# Qwiic_OLED_Breakout.net
KiCad netlist of a schematic drawn in EAGLE
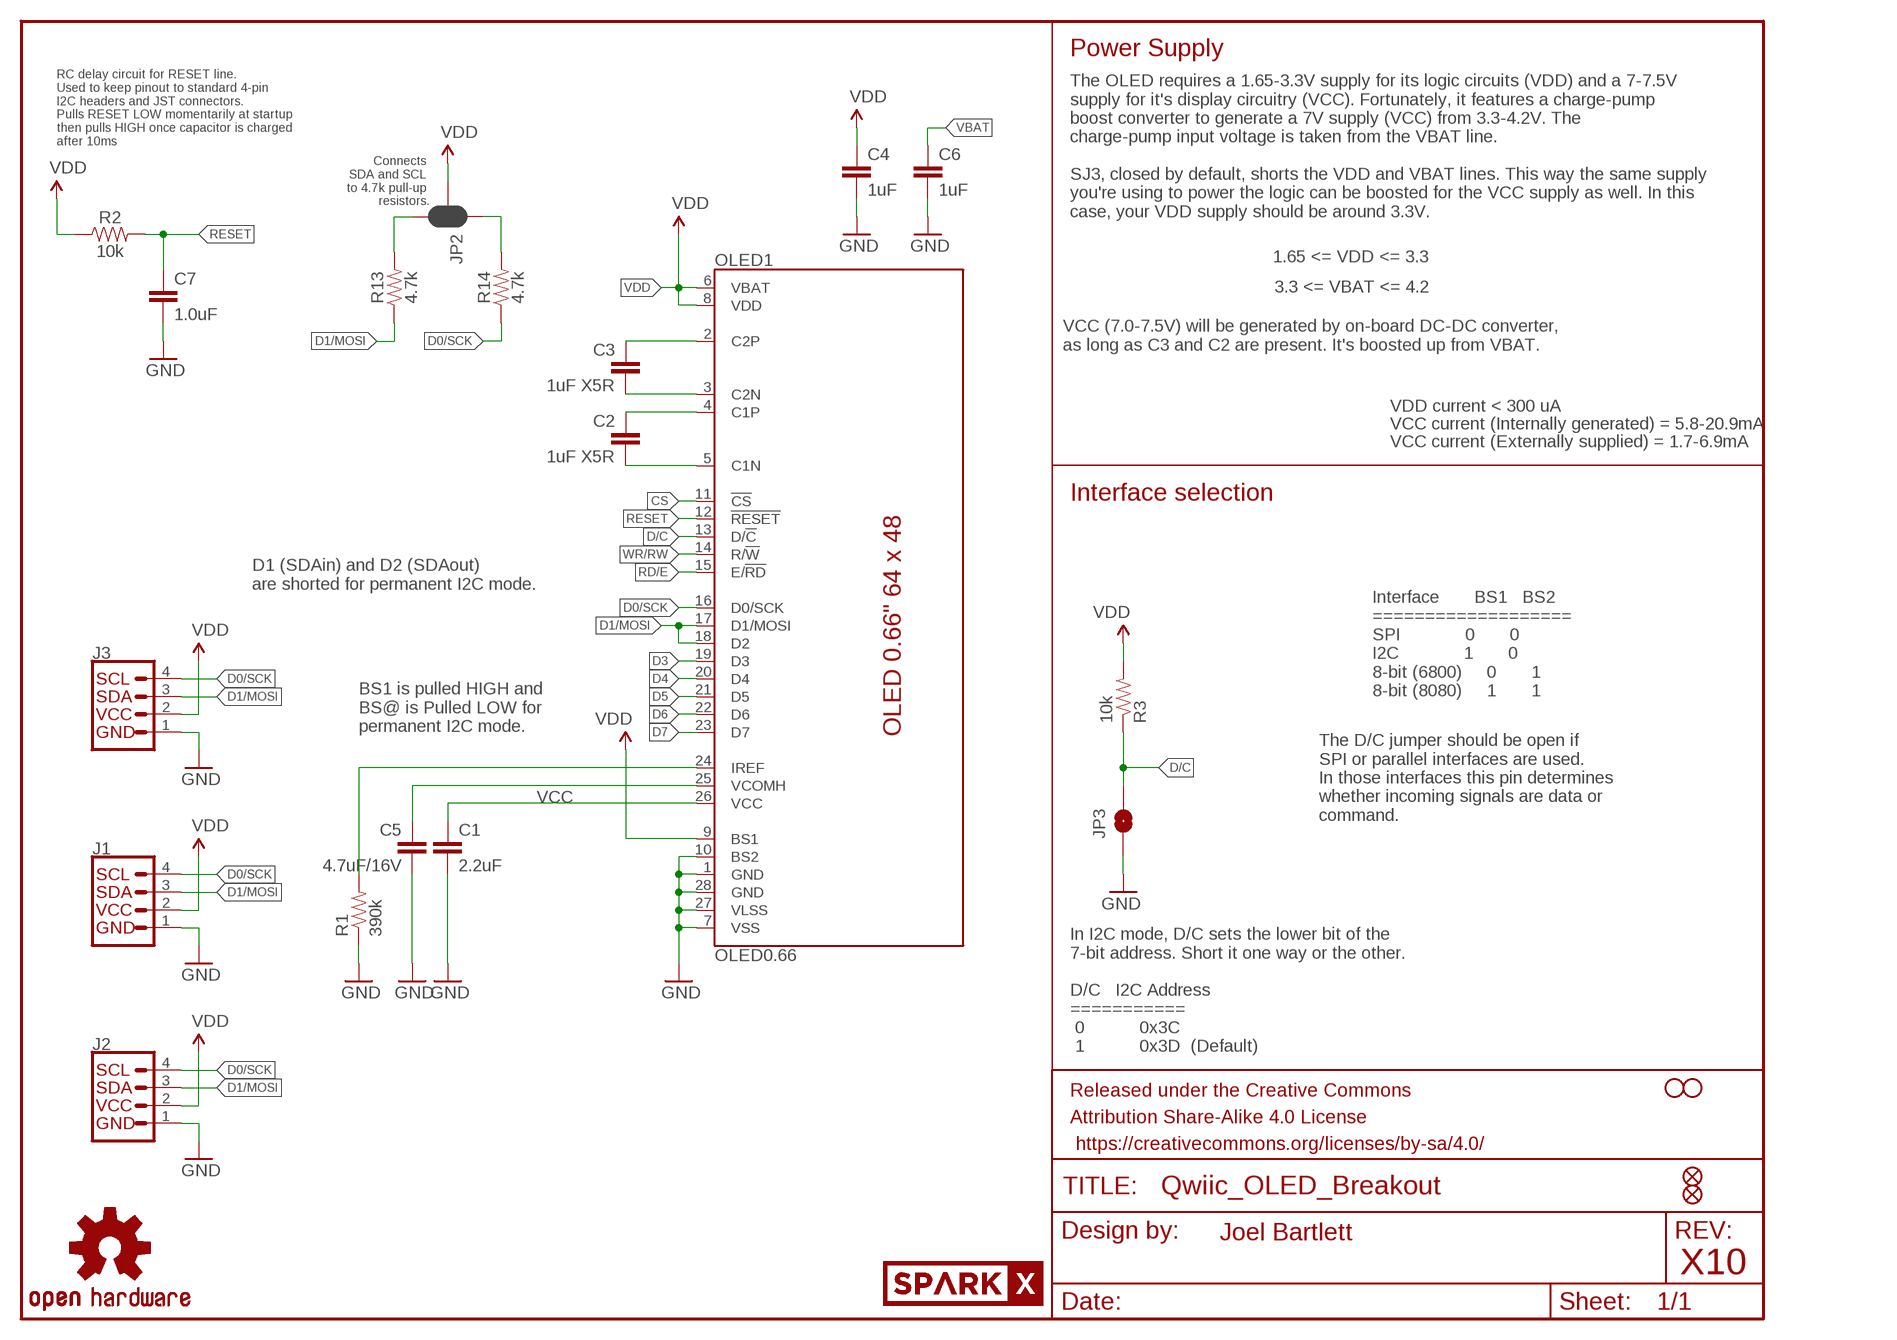
[diagram p0: schematic, sheet 1]

(export (version "E")
  (design (tool "Eeschema 10.0.6"))
  (components
    (comp (ref "C1")
      (value "2.2uF")
      (footprint "eagle-import:0805")
      (libsource (lib "eagle-import") (part "CAP0805"))
    )
    (comp (ref "C2")
      (value "1uF X5R")
      (footprint "eagle-import:0805")
      (libsource (lib "eagle-import") (part "CAP0805"))
    )
    (comp (ref "C3")
      (value "1uF X5R")
      (footprint "eagle-import:0805")
      (libsource (lib "eagle-import") (part "CAP0805"))
    )
    (comp (ref "C4")
      (value "1uF")
      (footprint "eagle-import:0603-CAP")
      (libsource (lib "eagle-import") (part "CAP0603-CAP"))
    )
    (comp (ref "C5")
      (value "4.7uF/16V")
      (footprint "eagle-import:1206")
      (libsource (lib "eagle-import") (part "CAP1206"))
    )
    (comp (ref "C6")
      (value "1uF")
      (footprint "eagle-import:0603-CAP")
      (libsource (lib "eagle-import") (part "CAP0603-CAP"))
    )
    (comp (ref "C7")
      (value "1.0uF")
      (footprint "eagle-import:0603")
      (libsource (lib "eagle-import") (part "1.0UF-0603-16V-10%"))
    )
    (comp (ref "FID1")
      (value "FIDUCIAL1X2")
      (footprint "eagle-import:FIDUCIAL-1X2")
      (libsource (lib "eagle-import") (part "FIDUCIAL1X2"))
    )
    (comp (ref "FID2")
      (value "FIDUCIAL1X2")
      (footprint "eagle-import:FIDUCIAL-1X2")
      (libsource (lib "eagle-import") (part "FIDUCIAL1X2"))
    )
    (comp (ref "FRAME1")
      (value "FRAME-LETTER")
      (footprint "eagle-import:CREATIVE_COMMONS")
      (libsource (lib "eagle-import") (part "FRAME-LETTER"))
    )
    (comp (ref "H1")
      (value "STAND-OFF")
      (footprint "eagle-import:STAND-OFF")
      (libsource (lib "eagle-import") (part "STAND-OFF"))
    )
    (comp (ref "H2")
      (value "STAND-OFF")
      (footprint "eagle-import:STAND-OFF")
      (libsource (lib "eagle-import") (part "STAND-OFF"))
    )
    (comp (ref "J1")
      (value "I2C_STANDARDJS-1MM")
      (footprint "eagle-import:1X04_1MM_RA")
      (libsource (lib "eagle-import") (part "I2C_STANDARDJS-1MM"))
    )
    (comp (ref "J2")
      (value "I2C_STANDARDJS-1MM")
      (footprint "eagle-import:1X04_1MM_RA")
      (libsource (lib "eagle-import") (part "I2C_STANDARDJS-1MM"))
    )
    (comp (ref "J3")
      (value "I2C_STANDARD_NO_SILK")
      (footprint "eagle-import:1X04_NO_SILK")
      (libsource (lib "eagle-import") (part "I2C_STANDARD_NO_SILK"))
    )
    (comp (ref "JP2")
      (value "JUMPER-SMT_3_2-NC_PASTE_SILK")
      (footprint "eagle-import:SMT-JUMPER_3_2-NC_PASTE_SILK")
      (libsource (lib "eagle-import") (part "JUMPER-SMT_3_2-NC_PASTE_SILK"))
    )
    (comp (ref "JP3")
      (value "JUMPER-SMT_2_NO_SILK")
      (footprint "eagle-import:SMT-JUMPER_2_NO_SILK")
      (libsource (lib "eagle-import") (part "JUMPER-SMT_2_NO_SILK"))
    )
    (comp (ref "LOGO3")
      (value "OSHW-LOGOS")
      (footprint "eagle-import:OSHW-LOGO-S")
      (libsource (lib "eagle-import") (part "OSHW-LOGOS"))
    )
    (comp (ref "OLED1")
      (value "OLED0.66")
      (footprint "eagle-import:OLED-0.66-64X48")
      (libsource (lib "eagle-import") (part "OLED0.66"))
    )
    (comp (ref "R1")
      (value "390k")
      (footprint "eagle-import:0603-RES")
      (libsource (lib "eagle-import") (part "RESISTOR0603-RES"))
    )
    (comp (ref "R2")
      (value "10k")
      (footprint "eagle-import:0603")
      (libsource (lib "eagle-import") (part "10KOHM-0603-1/10W-1%"))
    )
    (comp (ref "R3")
      (value "10k")
      (footprint "eagle-import:0603-RES")
      (libsource (lib "eagle-import") (part "RESISTOR0603-RES"))
    )
    (comp (ref "R13")
      (value "4.7k")
      (footprint "eagle-import:0603")
      (libsource (lib "eagle-import") (part "4.7KOHM-0603-1/10W-1%"))
    )
    (comp (ref "R14")
      (value "4.7k")
      (footprint "eagle-import:0603")
      (libsource (lib "eagle-import") (part "4.7KOHM-0603-1/10W-1%"))
    )
    (comp (ref "U$1")
      (value "SPARKX-LOGO4")
      (footprint "eagle-import:SPARKX-MEDIUM")
      (libsource (lib "eagle-import") (part "SPARKX-LOGO4"))
    )
    (comp (ref "U$3")
      (value "SPARKX-LOGO2")
      (footprint "eagle-import:SPARKX-TINY")
      (libsource (lib "eagle-import") (part "SPARKX-LOGO2"))
    )
  )
  (nets
    (net (code "1") (name "/VCC") (class "Default")
      (node (ref "C1") (pin "1") (pinfunction "1_1") (pintype "passive"))
      (node (ref "OLED1") (pin "26") (pinfunction "VCC_26") (pintype "bidirectional"))
    )
    (net (code "2") (name "CS") (class "Default")
      (node (ref "OLED1") (pin "11") (pinfunction "~{CS}_11") (pintype "bidirectional"))
    )
    (net (code "3") (name "D0{slash}SCK") (class "Default")
      (node (ref "J1") (pin "4") (pinfunction "SCL_4") (pintype "passive"))
      (node (ref "J2") (pin "4") (pinfunction "SCL_4") (pintype "passive"))
      (node (ref "J3") (pin "4") (pinfunction "SCL_4") (pintype "passive"))
      (node (ref "OLED1") (pin "16") (pinfunction "D0/SCK_16") (pintype "bidirectional"))
      (node (ref "R14") (pin "1") (pinfunction "1_1") (pintype "passive"))
    )
    (net (code "4") (name "D1{slash}MOSI") (class "Default")
      (node (ref "J1") (pin "3") (pinfunction "SDA_3") (pintype "passive"))
      (node (ref "J2") (pin "3") (pinfunction "SDA_3") (pintype "passive"))
      (node (ref "J3") (pin "3") (pinfunction "SDA_3") (pintype "passive"))
      (node (ref "OLED1") (pin "17") (pinfunction "D1/MOSI_17") (pintype "bidirectional"))
      (node (ref "OLED1") (pin "18") (pinfunction "D2_18") (pintype "bidirectional"))
      (node (ref "R13") (pin "1") (pinfunction "1_1") (pintype "passive"))
    )
    (net (code "5") (name "D3") (class "Default")
      (node (ref "OLED1") (pin "19") (pinfunction "D3_19") (pintype "bidirectional"))
    )
    (net (code "6") (name "D4") (class "Default")
      (node (ref "OLED1") (pin "20") (pinfunction "D4_20") (pintype "bidirectional"))
    )
    (net (code "7") (name "D5") (class "Default")
      (node (ref "OLED1") (pin "21") (pinfunction "D5_21") (pintype "bidirectional"))
    )
    (net (code "8") (name "D6") (class "Default")
      (node (ref "OLED1") (pin "22") (pinfunction "D6_22") (pintype "bidirectional"))
    )
    (net (code "9") (name "D7") (class "Default")
      (node (ref "OLED1") (pin "23") (pinfunction "D7_23") (pintype "bidirectional"))
    )
    (net (code "10") (name "D{slash}C") (class "Default")
      (node (ref "JP3") (pin "2") (pinfunction "2_2") (pintype "passive"))
      (node (ref "OLED1") (pin "13") (pinfunction "D/~{C}_13") (pintype "bidirectional"))
      (node (ref "R3") (pin "1") (pinfunction "1_1") (pintype "passive"))
    )
    (net (code "11") (name "GND") (class "Default")
      (node (ref "C1") (pin "2") (pinfunction "2_2") (pintype "passive"))
      (node (ref "C4") (pin "2") (pinfunction "2_2") (pintype "passive"))
      (node (ref "C5") (pin "2") (pinfunction "2_2") (pintype "passive"))
      (node (ref "C6") (pin "2") (pinfunction "2_2") (pintype "passive"))
      (node (ref "C7") (pin "2") (pinfunction "2_2") (pintype "passive"))
      (node (ref "J1") (pin "1") (pinfunction "GND_1") (pintype "power_in"))
      (node (ref "J2") (pin "1") (pinfunction "GND_1") (pintype "power_in"))
      (node (ref "J3") (pin "1") (pinfunction "GND_1") (pintype "power_in"))
      (node (ref "JP3") (pin "1") (pinfunction "1_1") (pintype "passive"))
      (node (ref "OLED1") (pin "1") (pinfunction "GND_1") (pintype "bidirectional"))
      (node (ref "OLED1") (pin "10") (pinfunction "BS2_10") (pintype "bidirectional"))
      (node (ref "OLED1") (pin "27") (pinfunction "VLSS_27") (pintype "bidirectional"))
      (node (ref "OLED1") (pin "28") (pinfunction "GND_28") (pintype "bidirectional"))
      (node (ref "OLED1") (pin "7") (pinfunction "VSS_7") (pintype "bidirectional"))
      (node (ref "R1") (pin "1") (pinfunction "1_1") (pintype "passive"))
    )
    (net (code "12") (name "Net-(JP2-Pad1)") (class "Default")
      (node (ref "JP2") (pin "1") (pinfunction "1_1") (pintype "passive"))
      (node (ref "R14") (pin "2") (pinfunction "2_2") (pintype "passive"))
    )
    (net (code "13") (name "Net-(JP2-Pad3)") (class "Default")
      (node (ref "JP2") (pin "3") (pinfunction "3_3") (pintype "passive"))
      (node (ref "R13") (pin "2") (pinfunction "2_2") (pintype "passive"))
    )
    (net (code "14") (name "Net-(OLED1-C1N)") (class "Default")
      (node (ref "C2") (pin "2") (pinfunction "2_2") (pintype "passive"))
      (node (ref "OLED1") (pin "5") (pinfunction "C1N_5") (pintype "bidirectional"))
    )
    (net (code "15") (name "Net-(OLED1-C1P)") (class "Default")
      (node (ref "C2") (pin "1") (pinfunction "1_1") (pintype "passive"))
      (node (ref "OLED1") (pin "4") (pinfunction "C1P_4") (pintype "bidirectional"))
    )
    (net (code "16") (name "Net-(OLED1-C2N)") (class "Default")
      (node (ref "C3") (pin "2") (pinfunction "2_2") (pintype "passive"))
      (node (ref "OLED1") (pin "3") (pinfunction "C2N_3") (pintype "bidirectional"))
    )
    (net (code "17") (name "Net-(OLED1-C2P)") (class "Default")
      (node (ref "C3") (pin "1") (pinfunction "1_1") (pintype "passive"))
      (node (ref "OLED1") (pin "2") (pinfunction "C2P_2") (pintype "bidirectional"))
    )
    (net (code "18") (name "Net-(OLED1-IREF)") (class "Default")
      (node (ref "OLED1") (pin "24") (pinfunction "IREF_24") (pintype "bidirectional"))
      (node (ref "R1") (pin "2") (pinfunction "2_2") (pintype "passive"))
    )
    (net (code "19") (name "Net-(OLED1-VCOMH)") (class "Default")
      (node (ref "C5") (pin "1") (pinfunction "1_1") (pintype "passive"))
      (node (ref "OLED1") (pin "25") (pinfunction "VCOMH_25") (pintype "bidirectional"))
    )
    (net (code "20") (name "RD{slash}E") (class "Default")
      (node (ref "OLED1") (pin "15") (pinfunction "E/~{RD}_15") (pintype "bidirectional"))
    )
    (net (code "21") (name "RESET") (class "Default")
      (node (ref "C7") (pin "1") (pinfunction "1_1") (pintype "passive"))
      (node (ref "OLED1") (pin "12") (pinfunction "~{RESET}_12") (pintype "bidirectional"))
      (node (ref "R2") (pin "2") (pinfunction "2_2") (pintype "passive"))
    )
    (net (code "22") (name "VBAT") (class "Default")
      (node (ref "C6") (pin "1") (pinfunction "1_1") (pintype "passive"))
    )
    (net (code "23") (name "VDD") (class "Default")
      (node (ref "C4") (pin "1") (pinfunction "1_1") (pintype "passive"))
      (node (ref "J1") (pin "2") (pinfunction "VCC_2") (pintype "power_in"))
      (node (ref "J2") (pin "2") (pinfunction "VCC_2") (pintype "power_in"))
      (node (ref "J3") (pin "2") (pinfunction "VCC_2") (pintype "power_in"))
      (node (ref "JP2") (pin "2") (pinfunction "2_2") (pintype "passive"))
      (node (ref "OLED1") (pin "6") (pinfunction "VBAT_6") (pintype "bidirectional"))
      (node (ref "OLED1") (pin "8") (pinfunction "VDD_8") (pintype "bidirectional"))
      (node (ref "OLED1") (pin "9") (pinfunction "BS1_9") (pintype "bidirectional"))
      (node (ref "R2") (pin "1") (pinfunction "1_1") (pintype "passive"))
      (node (ref "R3") (pin "2") (pinfunction "2_2") (pintype "passive"))
    )
    (net (code "24") (name "WR{slash}RW") (class "Default")
      (node (ref "OLED1") (pin "14") (pinfunction "R/~{W}_14") (pintype "bidirectional"))
    )
  )
)
